# schematic.net
KiCad netlist of a schematic drawn in EasyEDA
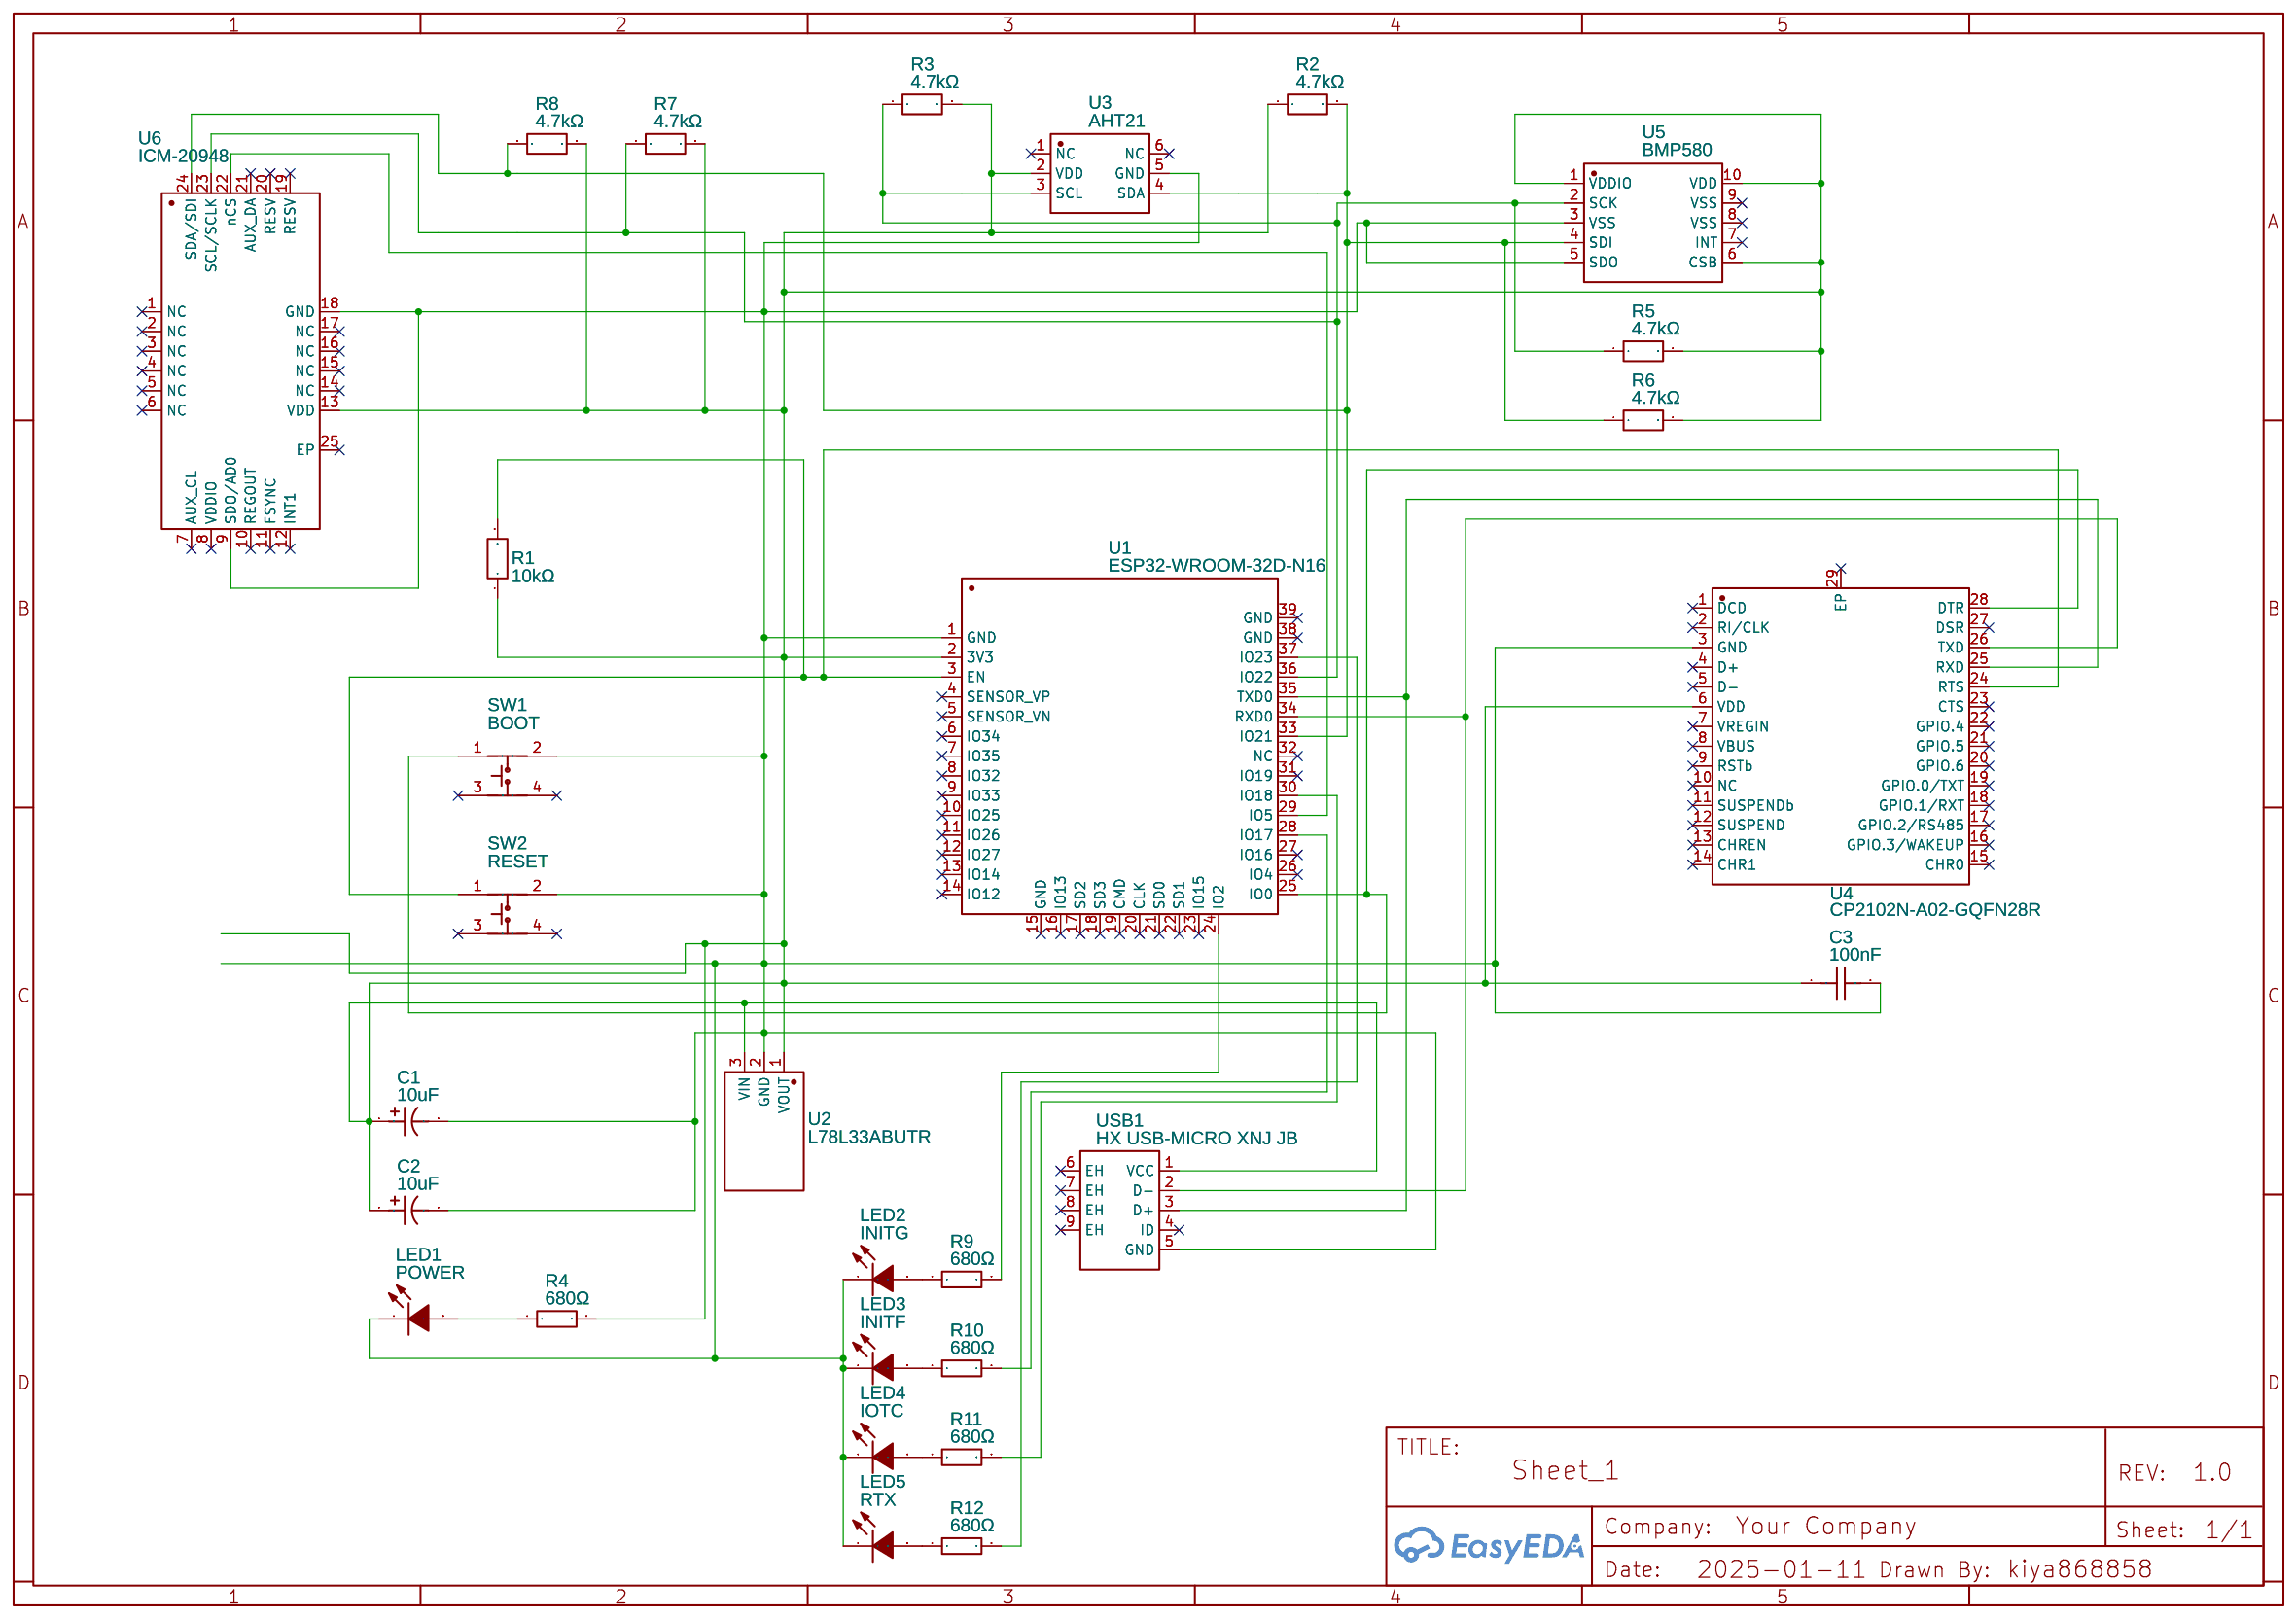
[diagram p0: schematic sheet]

(export (version "E")
  (design (tool "Eeschema 10.0.6"))
  (components
    (comp (ref "C1")
      (value "10uF")
      (fields (field (name "Manufacturer Part") "T491A106K010AT") (field (name "Manufacturer") "KEMET(基美)"))
      (libsource (lib "") (part "T491A106K010AT_C1508940"))
    )
    (comp (ref "C2")
      (value "10uF")
      (fields (field (name "Manufacturer Part") "T491A106K010AT") (field (name "Manufacturer") "KEMET(基美)"))
      (libsource (lib "") (part "T491A106K010AT_C1508940"))
    )
    (comp (ref "C3")
      (value "100nF")
      (fields
        (field (name "Manufacturer Part") "GRM188R71H104KA93D")
        (field (name "Manufacturer") "muRata(村田)")
      )
      (libsource (lib "") (part "GRM188R71H104KA93D"))
    )
    (comp (ref "LED1")
      (value "POWER")
      (fields
        (field (name "Manufacturer Part") "LTST-C193KGKT-5A")
        (field (name "Manufacturer") "LITEON(光宝)")
      )
      (libsource (lib "") (part "LTST-C193KGKT-5A"))
    )
    (comp (ref "LED2")
      (value "INITG")
      (fields
        (field (name "Manufacturer Part") "LTST-C193KGKT-5A")
        (field (name "Manufacturer") "LITEON(光宝)")
      )
      (libsource (lib "") (part "LTST-C193KGKT-5A"))
    )
    (comp (ref "LED3")
      (value "INITF")
      (fields
        (field (name "Manufacturer Part") "LTST-C193KGKT-5A")
        (field (name "Manufacturer") "LITEON(光宝)")
      )
      (libsource (lib "") (part "LTST-C193KGKT-5A"))
    )
    (comp (ref "LED4")
      (value "IOTC")
      (fields
        (field (name "Manufacturer Part") "LTST-C193KGKT-5A")
        (field (name "Manufacturer") "LITEON(光宝)")
      )
      (libsource (lib "") (part "LTST-C193KGKT-5A"))
    )
    (comp (ref "LED5")
      (value "RTX")
      (fields
        (field (name "Manufacturer Part") "LTST-C193KGKT-5A")
        (field (name "Manufacturer") "LITEON(光宝)")
      )
      (libsource (lib "") (part "LTST-C193KGKT-5A"))
    )
    (comp (ref "R1")
      (value "10kΩ")
      (fields
        (field (name "Manufacturer Part") "CRCW080510K0FKEAHP")
        (field (name "Manufacturer") "VISHAY(威世)")
      )
      (libsource (lib "") (part "CRCW080510K0FKEAHP"))
    )
    (comp (ref "R2")
      (value "4.7kΩ")
      (fields
        (field (name "Manufacturer Part") "CRCW08054K70JNEA")
        (field (name "Manufacturer") "VISHAY(威世)")
      )
      (libsource (lib "") (part "CRCW08054K70JNEA"))
    )
    (comp (ref "R3")
      (value "4.7kΩ")
      (fields
        (field (name "Manufacturer Part") "CRCW08054K70JNEA")
        (field (name "Manufacturer") "VISHAY(威世)")
      )
      (libsource (lib "") (part "CRCW08054K70JNEA"))
    )
    (comp (ref "R4")
      (value "680Ω")
      (fields (field (name "Manufacturer Part") "RC0603FR-07680RL") (field (name "Manufacturer") "YAGEO(国巨)"))
      (libsource (lib "") (part "RC0603FR-07680RL"))
    )
    (comp (ref "R5")
      (value "4.7kΩ")
      (fields
        (field (name "Manufacturer Part") "CRCW08054K70JNEA")
        (field (name "Manufacturer") "VISHAY(威世)")
      )
      (libsource (lib "") (part "CRCW08054K70JNEA"))
    )
    (comp (ref "R6")
      (value "4.7kΩ")
      (fields
        (field (name "Manufacturer Part") "CRCW08054K70JNEA")
        (field (name "Manufacturer") "VISHAY(威世)")
      )
      (libsource (lib "") (part "CRCW08054K70JNEA"))
    )
    (comp (ref "R7")
      (value "4.7kΩ")
      (fields
        (field (name "Manufacturer Part") "CRCW08054K70JNEA")
        (field (name "Manufacturer") "VISHAY(威世)")
      )
      (libsource (lib "") (part "CRCW08054K70JNEA"))
    )
    (comp (ref "R8")
      (value "4.7kΩ")
      (fields
        (field (name "Manufacturer Part") "CRCW08054K70JNEA")
        (field (name "Manufacturer") "VISHAY(威世)")
      )
      (libsource (lib "") (part "CRCW08054K70JNEA"))
    )
    (comp (ref "R9")
      (value "680Ω")
      (fields (field (name "Manufacturer Part") "RC0603FR-07680RL") (field (name "Manufacturer") "YAGEO(国巨)"))
      (libsource (lib "") (part "RC0603FR-07680RL"))
    )
    (comp (ref "R10")
      (value "680Ω")
      (fields (field (name "Manufacturer Part") "RC0603FR-07680RL") (field (name "Manufacturer") "YAGEO(国巨)"))
      (libsource (lib "") (part "RC0603FR-07680RL"))
    )
    (comp (ref "R11")
      (value "680Ω")
      (fields (field (name "Manufacturer Part") "RC0603FR-07680RL") (field (name "Manufacturer") "YAGEO(国巨)"))
      (libsource (lib "") (part "RC0603FR-07680RL"))
    )
    (comp (ref "R12")
      (value "680Ω")
      (fields (field (name "Manufacturer Part") "RC0603FR-07680RL") (field (name "Manufacturer") "YAGEO(国巨)"))
      (libsource (lib "") (part "RC0603FR-07680RL"))
    )
    (comp (ref "SW1")
      (value "BOOT")
      (fields
        (field (name "Manufacturer Part") "SKRPABE010")
        (field (name "Manufacturer") "ALPSALPINE(阿尔卑斯阿尔派)")
      )
      (libsource (lib "") (part "SKRPABE010"))
    )
    (comp (ref "SW2")
      (value "RESET")
      (fields
        (field (name "Manufacturer Part") "SKRPABE010")
        (field (name "Manufacturer") "ALPSALPINE(阿尔卑斯阿尔派)")
      )
      (libsource (lib "") (part "SKRPABE010"))
    )
    (comp (ref "U1")
      (value "ESP32-WROOM-32D-N16")
      (fields (field (name "Manufacturer Part") "ESP32-WROOM-32D-N16-被合并"))
      (libsource (lib "") (part "ESP32-WROOM-32D-N16"))
    )
    (comp (ref "U2")
      (value "L78L33ABUTR")
      (fields (field (name "Manufacturer") "ST(意法半导体)"))
      (libsource (lib "") (part "L78L33ABUTR"))
    )
    (comp (ref "U3")
      (value "AHT21")
      (fields (field (name "Manufacturer") "广州奥松"))
      (libsource (lib "") (part "AHT21"))
    )
    (comp (ref "U4")
      (value "CP2102N-A02-GQFN28R")
      (fields (field (name "Manufacturer") "SKYWORKS/SILICON LABS(芯科)"))
      (libsource (lib "") (part "CP2102N-A02-GQFN28R"))
    )
    (comp (ref "U5")
      (value "BMP580")
      (fields (field (name "Manufacturer") "Bosch(博世)"))
      (libsource (lib "") (part "BMP580"))
    )
    (comp (ref "U6")
      (value "ICM-20948")
      (fields (field (name "Manufacturer") "TDK InvenSense(应美盛)"))
      (libsource (lib "") (part "ICM-20948"))
    )
    (comp (ref "USB1")
      (value "HX USB-MICRO XNJ JB")
      (fields (field (name "Manufacturer") "hanxia(韩下)"))
      (libsource (lib "") (part "HX USB-MICRO XNJ JB"))
    )
  )
  (nets
    (net (code "1") (name "Net-(LED1-+)") (class "Default")
      (node (ref "LED1") (pin "2") (pinfunction "+_2") (pintype "unspecified"))
      (node (ref "R4") (pin "1") (pinfunction "1_1") (pintype "input"))
    )
    (net (code "2") (name "Net-(LED1--)") (class "Default")
      (node (ref "C1") (pin "2") (pinfunction "2_2") (pintype "input"))
      (node (ref "C2") (pin "2") (pinfunction "2_2") (pintype "input"))
      (node (ref "C3") (pin "2") (pinfunction "2_2") (pintype "unspecified"))
      (node (ref "LED1") (pin "1") (pinfunction "-_1") (pintype "unspecified"))
      (node (ref "LED2") (pin "1") (pinfunction "-_1") (pintype "unspecified"))
      (node (ref "LED3") (pin "1") (pinfunction "-_1") (pintype "unspecified"))
      (node (ref "LED4") (pin "1") (pinfunction "-_1") (pintype "unspecified"))
      (node (ref "LED5") (pin "1") (pinfunction "-_1") (pintype "unspecified"))
      (node (ref "SW1") (pin "2") (pinfunction "2_2") (pintype "unspecified"))
      (node (ref "SW2") (pin "2") (pinfunction "2_2") (pintype "unspecified"))
      (node (ref "U1") (pin "1") (pinfunction "GND_1") (pintype "unspecified"))
      (node (ref "U2") (pin "2") (pinfunction "GND_2") (pintype "unspecified"))
      (node (ref "U3") (pin "5") (pinfunction "GND_5") (pintype "unspecified"))
      (node (ref "U4") (pin "3") (pinfunction "GND_3") (pintype "unspecified"))
      (node (ref "U5") (pin "3") (pinfunction "VSS_3") (pintype "unspecified"))
      (node (ref "U5") (pin "5") (pinfunction "SDO_5") (pintype "unspecified"))
      (node (ref "U6") (pin "18") (pinfunction "GND_18") (pintype "unspecified"))
      (node (ref "U6") (pin "9") (pinfunction "SDO/AD0_9") (pintype "unspecified"))
      (node (ref "USB1") (pin "5") (pinfunction "GND_5") (pintype "input"))
    )
    (net (code "3") (name "Net-(LED2-+)") (class "Default")
      (node (ref "LED2") (pin "2") (pinfunction "+_2") (pintype "unspecified"))
      (node (ref "R9") (pin "1") (pinfunction "1_1") (pintype "input"))
    )
    (net (code "4") (name "Net-(LED3-+)") (class "Default")
      (node (ref "LED3") (pin "2") (pinfunction "+_2") (pintype "unspecified"))
      (node (ref "R10") (pin "1") (pinfunction "1_1") (pintype "input"))
    )
    (net (code "5") (name "Net-(LED4-+)") (class "Default")
      (node (ref "LED4") (pin "2") (pinfunction "+_2") (pintype "unspecified"))
      (node (ref "R11") (pin "1") (pinfunction "1_1") (pintype "input"))
    )
    (net (code "6") (name "Net-(LED5-+)") (class "Default")
      (node (ref "LED5") (pin "2") (pinfunction "+_2") (pintype "unspecified"))
      (node (ref "R12") (pin "1") (pinfunction "1_1") (pintype "input"))
    )
    (net (code "7") (name "Net-(U1-3V3)") (class "Default")
      (node (ref "C1") (pin "1") (pinfunction "1_1") (pintype "input"))
      (node (ref "C2") (pin "1") (pinfunction "1_1") (pintype "input"))
      (node (ref "C3") (pin "1") (pinfunction "1_1") (pintype "unspecified"))
      (node (ref "R1") (pin "1") (pinfunction "1_1") (pintype "unspecified"))
      (node (ref "R2") (pin "1") (pinfunction "1_1") (pintype "unspecified"))
      (node (ref "R3") (pin "2") (pinfunction "2_2") (pintype "unspecified"))
      (node (ref "R4") (pin "2") (pinfunction "2_2") (pintype "input"))
      (node (ref "R5") (pin "2") (pinfunction "2_2") (pintype "unspecified"))
      (node (ref "R6") (pin "2") (pinfunction "2_2") (pintype "unspecified"))
      (node (ref "R7") (pin "2") (pinfunction "2_2") (pintype "unspecified"))
      (node (ref "R8") (pin "2") (pinfunction "2_2") (pintype "unspecified"))
      (node (ref "U1") (pin "2") (pinfunction "3V3_2") (pintype "unspecified"))
      (node (ref "U2") (pin "1") (pinfunction "VOUT_1") (pintype "unspecified"))
      (node (ref "U2") (pin "3") (pinfunction "VIN_3") (pintype "unspecified"))
      (node (ref "U3") (pin "2") (pinfunction "VDD_2") (pintype "unspecified"))
      (node (ref "U4") (pin "6") (pinfunction "VDD_6") (pintype "unspecified"))
      (node (ref "U5") (pin "1") (pinfunction "VDDIO_1") (pintype "unspecified"))
      (node (ref "U5") (pin "10") (pinfunction "VDD_10") (pintype "unspecified"))
      (node (ref "U5") (pin "6") (pinfunction "CSB_6") (pintype "unspecified"))
      (node (ref "U6") (pin "13") (pinfunction "VDD_13") (pintype "unspecified"))
      (node (ref "USB1") (pin "1") (pinfunction "VCC_1") (pintype "input"))
    )
    (net (code "8") (name "Net-(U1-EN)") (class "Default")
      (node (ref "R1") (pin "2") (pinfunction "2_2") (pintype "unspecified"))
      (node (ref "SW2") (pin "1") (pinfunction "1_1") (pintype "unspecified"))
      (node (ref "U1") (pin "3") (pinfunction "EN_3") (pintype "unspecified"))
      (node (ref "U4") (pin "24") (pinfunction "RTS_24") (pintype "unspecified"))
    )
    (net (code "9") (name "Net-(U1-IO0)") (class "Default")
      (node (ref "SW1") (pin "1") (pinfunction "1_1") (pintype "unspecified"))
      (node (ref "U1") (pin "25") (pinfunction "IO0_25") (pintype "unspecified"))
      (node (ref "U4") (pin "28") (pinfunction "DTR_28") (pintype "unspecified"))
    )
    (net (code "10") (name "Net-(U1-IO2)") (class "Default")
      (node (ref "R9") (pin "2") (pinfunction "2_2") (pintype "input"))
      (node (ref "U1") (pin "24") (pinfunction "IO2_24") (pintype "unspecified"))
    )
    (net (code "11") (name "Net-(U1-IO5)") (class "Default")
      (node (ref "U1") (pin "29") (pinfunction "IO5_29") (pintype "unspecified"))
      (node (ref "U6") (pin "22") (pinfunction "nCS_22") (pintype "unspecified"))
    )
    (net (code "12") (name "Net-(U1-IO17)") (class "Default")
      (node (ref "R10") (pin "2") (pinfunction "2_2") (pintype "input"))
      (node (ref "U1") (pin "28") (pinfunction "IO17_28") (pintype "unspecified"))
    )
    (net (code "13") (name "Net-(U1-IO18)") (class "Default")
      (node (ref "R11") (pin "2") (pinfunction "2_2") (pintype "input"))
      (node (ref "U1") (pin "30") (pinfunction "IO18_30") (pintype "unspecified"))
    )
    (net (code "14") (name "Net-(U1-IO21)") (class "Default")
      (node (ref "R2") (pin "2") (pinfunction "2_2") (pintype "unspecified"))
      (node (ref "R6") (pin "1") (pinfunction "1_1") (pintype "unspecified"))
      (node (ref "R8") (pin "1") (pinfunction "1_1") (pintype "unspecified"))
      (node (ref "U1") (pin "33") (pinfunction "IO21_33") (pintype "unspecified"))
      (node (ref "U3") (pin "4") (pinfunction "SDA_4") (pintype "unspecified"))
      (node (ref "U5") (pin "4") (pinfunction "SDI_4") (pintype "unspecified"))
      (node (ref "U6") (pin "24") (pinfunction "SDA/SDI_24") (pintype "unspecified"))
    )
    (net (code "15") (name "Net-(U1-IO22)") (class "Default")
      (node (ref "R3") (pin "1") (pinfunction "1_1") (pintype "unspecified"))
      (node (ref "R5") (pin "1") (pinfunction "1_1") (pintype "unspecified"))
      (node (ref "R7") (pin "1") (pinfunction "1_1") (pintype "unspecified"))
      (node (ref "U1") (pin "36") (pinfunction "IO22_36") (pintype "unspecified"))
      (node (ref "U3") (pin "3") (pinfunction "SCL_3") (pintype "unspecified"))
      (node (ref "U5") (pin "2") (pinfunction "SCK_2") (pintype "unspecified"))
      (node (ref "U6") (pin "23") (pinfunction "SCL/SCLK_23") (pintype "unspecified"))
    )
    (net (code "16") (name "Net-(U1-IO23)") (class "Default")
      (node (ref "R12") (pin "2") (pinfunction "2_2") (pintype "input"))
      (node (ref "U1") (pin "37") (pinfunction "IO23_37") (pintype "unspecified"))
    )
    (net (code "17") (name "Net-(U1-RXD0)") (class "Default")
      (node (ref "U1") (pin "34") (pinfunction "RXD0_34") (pintype "unspecified"))
      (node (ref "U4") (pin "26") (pinfunction "TXD_26") (pintype "unspecified"))
      (node (ref "USB1") (pin "2") (pinfunction "D-_2") (pintype "input"))
    )
    (net (code "18") (name "Net-(U1-TXD0)") (class "Default")
      (node (ref "U1") (pin "35") (pinfunction "TXD0_35") (pintype "unspecified"))
      (node (ref "U4") (pin "25") (pinfunction "RXD_25") (pintype "unspecified"))
      (node (ref "USB1") (pin "3") (pinfunction "D+_3") (pintype "input"))
    )
    (net (code "19") (name "unconnected-(SW1-Pad3)") (class "Default")
      (node (ref "SW1") (pin "3") (pinfunction "3_3") (pintype "unspecified+no_connect"))
    )
    (net (code "20") (name "unconnected-(SW1-Pad4)") (class "Default")
      (node (ref "SW1") (pin "4") (pinfunction "4_4") (pintype "unspecified+no_connect"))
    )
    (net (code "21") (name "unconnected-(SW2-Pad3)") (class "Default")
      (node (ref "SW2") (pin "3") (pinfunction "3_3") (pintype "unspecified+no_connect"))
    )
    (net (code "22") (name "unconnected-(SW2-Pad4)") (class "Default")
      (node (ref "SW2") (pin "4") (pinfunction "4_4") (pintype "unspecified+no_connect"))
    )
    (net (code "23") (name "unconnected-(U1-CLK-Pad20)") (class "Default")
      (node (ref "U1") (pin "20") (pinfunction "CLK_20") (pintype "unspecified+no_connect"))
    )
    (net (code "24") (name "unconnected-(U1-CMD-Pad19)") (class "Default")
      (node (ref "U1") (pin "19") (pinfunction "CMD_19") (pintype "unspecified+no_connect"))
    )
    (net (code "25") (name "unconnected-(U1-GND-Pad15)") (class "Default")
      (node (ref "U1") (pin "15") (pinfunction "GND_15") (pintype "unspecified+no_connect"))
    )
    (net (code "26") (name "unconnected-(U1-GND-Pad38)") (class "Default")
      (node (ref "U1") (pin "38") (pinfunction "GND_38") (pintype "unspecified+no_connect"))
    )
    (net (code "27") (name "unconnected-(U1-GND-Pad39)") (class "Default")
      (node (ref "U1") (pin "39") (pinfunction "GND_39") (pintype "unspecified+no_connect"))
    )
    (net (code "28") (name "unconnected-(U1-IO4-Pad26)") (class "Default")
      (node (ref "U1") (pin "26") (pinfunction "IO4_26") (pintype "unspecified+no_connect"))
    )
    (net (code "29") (name "unconnected-(U1-IO12-Pad14)") (class "Default")
      (node (ref "U1") (pin "14") (pinfunction "IO12_14") (pintype "unspecified+no_connect"))
    )
    (net (code "30") (name "unconnected-(U1-IO13-Pad16)") (class "Default")
      (node (ref "U1") (pin "16") (pinfunction "IO13_16") (pintype "unspecified+no_connect"))
    )
    (net (code "31") (name "unconnected-(U1-IO14-Pad13)") (class "Default")
      (node (ref "U1") (pin "13") (pinfunction "IO14_13") (pintype "unspecified+no_connect"))
    )
    (net (code "32") (name "unconnected-(U1-IO15-Pad23)") (class "Default")
      (node (ref "U1") (pin "23") (pinfunction "IO15_23") (pintype "unspecified+no_connect"))
    )
    (net (code "33") (name "unconnected-(U1-IO16-Pad27)") (class "Default")
      (node (ref "U1") (pin "27") (pinfunction "IO16_27") (pintype "unspecified+no_connect"))
    )
    (net (code "34") (name "unconnected-(U1-IO19-Pad31)") (class "Default")
      (node (ref "U1") (pin "31") (pinfunction "IO19_31") (pintype "unspecified+no_connect"))
    )
    (net (code "35") (name "unconnected-(U1-IO25-Pad10)") (class "Default")
      (node (ref "U1") (pin "10") (pinfunction "IO25_10") (pintype "unspecified+no_connect"))
    )
    (net (code "36") (name "unconnected-(U1-IO26-Pad11)") (class "Default")
      (node (ref "U1") (pin "11") (pinfunction "IO26_11") (pintype "unspecified+no_connect"))
    )
    (net (code "37") (name "unconnected-(U1-IO27-Pad12)") (class "Default")
      (node (ref "U1") (pin "12") (pinfunction "IO27_12") (pintype "unspecified+no_connect"))
    )
    (net (code "38") (name "unconnected-(U1-IO32-Pad8)") (class "Default")
      (node (ref "U1") (pin "8") (pinfunction "IO32_8") (pintype "unspecified+no_connect"))
    )
    (net (code "39") (name "unconnected-(U1-IO33-Pad9)") (class "Default")
      (node (ref "U1") (pin "9") (pinfunction "IO33_9") (pintype "unspecified+no_connect"))
    )
    (net (code "40") (name "unconnected-(U1-IO34-Pad6)") (class "Default")
      (node (ref "U1") (pin "6") (pinfunction "IO34_6") (pintype "unspecified+no_connect"))
    )
    (net (code "41") (name "unconnected-(U1-IO35-Pad7)") (class "Default")
      (node (ref "U1") (pin "7") (pinfunction "IO35_7") (pintype "unspecified+no_connect"))
    )
    (net (code "42") (name "unconnected-(U1-NC-Pad32)") (class "Default")
      (node (ref "U1") (pin "32") (pinfunction "NC_32") (pintype "unspecified+no_connect"))
    )
    (net (code "43") (name "unconnected-(U1-SD0-Pad21)") (class "Default")
      (node (ref "U1") (pin "21") (pinfunction "SD0_21") (pintype "unspecified+no_connect"))
    )
    (net (code "44") (name "unconnected-(U1-SD1-Pad22)") (class "Default")
      (node (ref "U1") (pin "22") (pinfunction "SD1_22") (pintype "unspecified+no_connect"))
    )
    (net (code "45") (name "unconnected-(U1-SD2-Pad17)") (class "Default")
      (node (ref "U1") (pin "17") (pinfunction "SD2_17") (pintype "unspecified+no_connect"))
    )
    (net (code "46") (name "unconnected-(U1-SD3-Pad18)") (class "Default")
      (node (ref "U1") (pin "18") (pinfunction "SD3_18") (pintype "unspecified+no_connect"))
    )
    (net (code "47") (name "unconnected-(U1-SENSOR_VN-Pad5)") (class "Default")
      (node (ref "U1") (pin "5") (pinfunction "SENSOR_VN_5") (pintype "unspecified+no_connect"))
    )
    (net (code "48") (name "unconnected-(U1-SENSOR_VP-Pad4)") (class "Default")
      (node (ref "U1") (pin "4") (pinfunction "SENSOR_VP_4") (pintype "unspecified+no_connect"))
    )
    (net (code "49") (name "unconnected-(U3-NC-Pad1)") (class "Default")
      (node (ref "U3") (pin "1") (pinfunction "NC_1") (pintype "unspecified+no_connect"))
    )
    (net (code "50") (name "unconnected-(U3-NC-Pad6)") (class "Default")
      (node (ref "U3") (pin "6") (pinfunction "NC_6") (pintype "unspecified+no_connect"))
    )
    (net (code "51") (name "unconnected-(U4-CHR0-Pad15)") (class "Default")
      (node (ref "U4") (pin "15") (pinfunction "CHR0_15") (pintype "unspecified+no_connect"))
    )
    (net (code "52") (name "unconnected-(U4-CHR1-Pad14)") (class "Default")
      (node (ref "U4") (pin "14") (pinfunction "CHR1_14") (pintype "unspecified+no_connect"))
    )
    (net (code "53") (name "unconnected-(U4-CHREN-Pad13)") (class "Default")
      (node (ref "U4") (pin "13") (pinfunction "CHREN_13") (pintype "unspecified+no_connect"))
    )
    (net (code "54") (name "unconnected-(U4-CTS-Pad23)") (class "Default")
      (node (ref "U4") (pin "23") (pinfunction "CTS_23") (pintype "unspecified+no_connect"))
    )
    (net (code "55") (name "unconnected-(U4-D+-Pad4)") (class "Default")
      (node (ref "U4") (pin "4") (pinfunction "D+_4") (pintype "unspecified+no_connect"))
    )
    (net (code "56") (name "unconnected-(U4-D--Pad5)") (class "Default")
      (node (ref "U4") (pin "5") (pinfunction "D-_5") (pintype "unspecified+no_connect"))
    )
    (net (code "57") (name "unconnected-(U4-DCD-Pad1)") (class "Default")
      (node (ref "U4") (pin "1") (pinfunction "DCD_1") (pintype "unspecified+no_connect"))
    )
    (net (code "58") (name "unconnected-(U4-DSR-Pad27)") (class "Default")
      (node (ref "U4") (pin "27") (pinfunction "DSR_27") (pintype "unspecified+no_connect"))
    )
    (net (code "59") (name "unconnected-(U4-EP-Pad29)") (class "Default")
      (node (ref "U4") (pin "29") (pinfunction "EP_29") (pintype "unspecified+no_connect"))
    )
    (net (code "60") (name "unconnected-(U4-GPIO.0{slash}TXT-Pad19)") (class "Default")
      (node (ref "U4") (pin "19") (pinfunction "GPIO.0/TXT_19") (pintype "unspecified+no_connect"))
    )
    (net (code "61") (name "unconnected-(U4-GPIO.1{slash}RXT-Pad18)") (class "Default")
      (node (ref "U4") (pin "18") (pinfunction "GPIO.1/RXT_18") (pintype "unspecified+no_connect"))
    )
    (net (code "62") (name "unconnected-(U4-GPIO.2{slash}RS485-Pad17)") (class "Default")
      (node (ref "U4") (pin "17") (pinfunction "GPIO.2/RS485_17") (pintype "unspecified+no_connect"))
    )
    (net (code "63") (name "unconnected-(U4-GPIO.3{slash}WAKEUP-Pad16)") (class "Default")
      (node (ref "U4") (pin "16") (pinfunction "GPIO.3/WAKEUP_16") (pintype "unspecified+no_connect"))
    )
    (net (code "64") (name "unconnected-(U4-GPIO.4-Pad22)") (class "Default")
      (node (ref "U4") (pin "22") (pinfunction "GPIO.4_22") (pintype "unspecified+no_connect"))
    )
    (net (code "65") (name "unconnected-(U4-GPIO.5-Pad21)") (class "Default")
      (node (ref "U4") (pin "21") (pinfunction "GPIO.5_21") (pintype "unspecified+no_connect"))
    )
    (net (code "66") (name "unconnected-(U4-GPIO.6-Pad20)") (class "Default")
      (node (ref "U4") (pin "20") (pinfunction "GPIO.6_20") (pintype "unspecified+no_connect"))
    )
    (net (code "67") (name "unconnected-(U4-NC-Pad10)") (class "Default")
      (node (ref "U4") (pin "10") (pinfunction "NC_10") (pintype "unspecified+no_connect"))
    )
    (net (code "68") (name "unconnected-(U4-RI{slash}CLK-Pad2)") (class "Default")
      (node (ref "U4") (pin "2") (pinfunction "RI/CLK_2") (pintype "unspecified+no_connect"))
    )
    (net (code "69") (name "unconnected-(U4-RSTb-Pad9)") (class "Default")
      (node (ref "U4") (pin "9") (pinfunction "RSTb_9") (pintype "unspecified+no_connect"))
    )
    (net (code "70") (name "unconnected-(U4-SUSPEND-Pad12)") (class "Default")
      (node (ref "U4") (pin "12") (pinfunction "SUSPEND_12") (pintype "unspecified+no_connect"))
    )
    (net (code "71") (name "unconnected-(U4-SUSPENDb-Pad11)") (class "Default")
      (node (ref "U4") (pin "11") (pinfunction "SUSPENDb_11") (pintype "unspecified+no_connect"))
    )
    (net (code "72") (name "unconnected-(U4-VBUS-Pad8)") (class "Default")
      (node (ref "U4") (pin "8") (pinfunction "VBUS_8") (pintype "unspecified+no_connect"))
    )
    (net (code "73") (name "unconnected-(U4-VREGIN-Pad7)") (class "Default")
      (node (ref "U4") (pin "7") (pinfunction "VREGIN_7") (pintype "unspecified+no_connect"))
    )
    (net (code "74") (name "unconnected-(U5-INT-Pad7)") (class "Default")
      (node (ref "U5") (pin "7") (pinfunction "INT_7") (pintype "unspecified+no_connect"))
    )
    (net (code "75") (name "unconnected-(U5-VSS-Pad8)") (class "Default")
      (node (ref "U5") (pin "8") (pinfunction "VSS_8") (pintype "unspecified+no_connect"))
    )
    (net (code "76") (name "unconnected-(U5-VSS-Pad9)") (class "Default")
      (node (ref "U5") (pin "9") (pinfunction "VSS_9") (pintype "unspecified+no_connect"))
    )
    (net (code "77") (name "unconnected-(U6-AUX_CL-Pad7)") (class "Default")
      (node (ref "U6") (pin "7") (pinfunction "AUX_CL_7") (pintype "unspecified+no_connect"))
    )
    (net (code "78") (name "unconnected-(U6-AUX_DA-Pad21)") (class "Default")
      (node (ref "U6") (pin "21") (pinfunction "AUX_DA_21") (pintype "unspecified+no_connect"))
    )
    (net (code "79") (name "unconnected-(U6-EP-Pad25)") (class "Default")
      (node (ref "U6") (pin "25") (pinfunction "EP_25") (pintype "unspecified+no_connect"))
    )
    (net (code "80") (name "unconnected-(U6-FSYNC-Pad11)") (class "Default")
      (node (ref "U6") (pin "11") (pinfunction "FSYNC_11") (pintype "unspecified+no_connect"))
    )
    (net (code "81") (name "unconnected-(U6-INT1-Pad12)") (class "Default")
      (node (ref "U6") (pin "12") (pinfunction "INT1_12") (pintype "unspecified+no_connect"))
    )
    (net (code "82") (name "unconnected-(U6-NC-Pad1)") (class "Default")
      (node (ref "U6") (pin "1") (pinfunction "NC_1") (pintype "unspecified+no_connect"))
    )
    (net (code "83") (name "unconnected-(U6-NC-Pad2)") (class "Default")
      (node (ref "U6") (pin "2") (pinfunction "NC_2") (pintype "unspecified+no_connect"))
    )
    (net (code "84") (name "unconnected-(U6-NC-Pad3)") (class "Default")
      (node (ref "U6") (pin "3") (pinfunction "NC_3") (pintype "unspecified+no_connect"))
    )
    (net (code "85") (name "unconnected-(U6-NC-Pad4)") (class "Default")
      (node (ref "U6") (pin "4") (pinfunction "NC_4") (pintype "unspecified+no_connect"))
    )
    (net (code "86") (name "unconnected-(U6-NC-Pad5)") (class "Default")
      (node (ref "U6") (pin "5") (pinfunction "NC_5") (pintype "unspecified+no_connect"))
    )
    (net (code "87") (name "unconnected-(U6-NC-Pad6)") (class "Default")
      (node (ref "U6") (pin "6") (pinfunction "NC_6") (pintype "unspecified+no_connect"))
    )
    (net (code "88") (name "unconnected-(U6-NC-Pad14)") (class "Default")
      (node (ref "U6") (pin "14") (pinfunction "NC_14") (pintype "unspecified+no_connect"))
    )
    (net (code "89") (name "unconnected-(U6-NC-Pad15)") (class "Default")
      (node (ref "U6") (pin "15") (pinfunction "NC_15") (pintype "unspecified+no_connect"))
    )
    (net (code "90") (name "unconnected-(U6-NC-Pad16)") (class "Default")
      (node (ref "U6") (pin "16") (pinfunction "NC_16") (pintype "unspecified+no_connect"))
    )
    (net (code "91") (name "unconnected-(U6-NC-Pad17)") (class "Default")
      (node (ref "U6") (pin "17") (pinfunction "NC_17") (pintype "unspecified+no_connect"))
    )
    (net (code "92") (name "unconnected-(U6-REGOUT-Pad10)") (class "Default")
      (node (ref "U6") (pin "10") (pinfunction "REGOUT_10") (pintype "unspecified+no_connect"))
    )
    (net (code "93") (name "unconnected-(U6-RESV-Pad19)") (class "Default")
      (node (ref "U6") (pin "19") (pinfunction "RESV_19") (pintype "unspecified+no_connect"))
    )
    (net (code "94") (name "unconnected-(U6-RESV-Pad20)") (class "Default")
      (node (ref "U6") (pin "20") (pinfunction "RESV_20") (pintype "unspecified+no_connect"))
    )
    (net (code "95") (name "unconnected-(U6-VDDIO-Pad8)") (class "Default")
      (node (ref "U6") (pin "8") (pinfunction "VDDIO_8") (pintype "unspecified+no_connect"))
    )
    (net (code "96") (name "unconnected-(USB1-EH-Pad6)") (class "Default")
      (node (ref "USB1") (pin "6") (pinfunction "EH_6") (pintype "unspecified+no_connect"))
    )
    (net (code "97") (name "unconnected-(USB1-EH-Pad7)") (class "Default")
      (node (ref "USB1") (pin "7") (pinfunction "EH_7") (pintype "unspecified+no_connect"))
    )
    (net (code "98") (name "unconnected-(USB1-EH-Pad8)") (class "Default")
      (node (ref "USB1") (pin "8") (pinfunction "EH_8") (pintype "unspecified+no_connect"))
    )
    (net (code "99") (name "unconnected-(USB1-EH-Pad9)") (class "Default")
      (node (ref "USB1") (pin "9") (pinfunction "EH_9") (pintype "unspecified+no_connect"))
    )
    (net (code "100") (name "unconnected-(USB1-ID-Pad4)") (class "Default")
      (node (ref "USB1") (pin "4") (pinfunction "ID_4") (pintype "input+no_connect"))
    )
  )
)
